# DEVICE-DESKTOP-910Q0FJ.net
KiCad netlist of a schematic drawn in Altium Designer
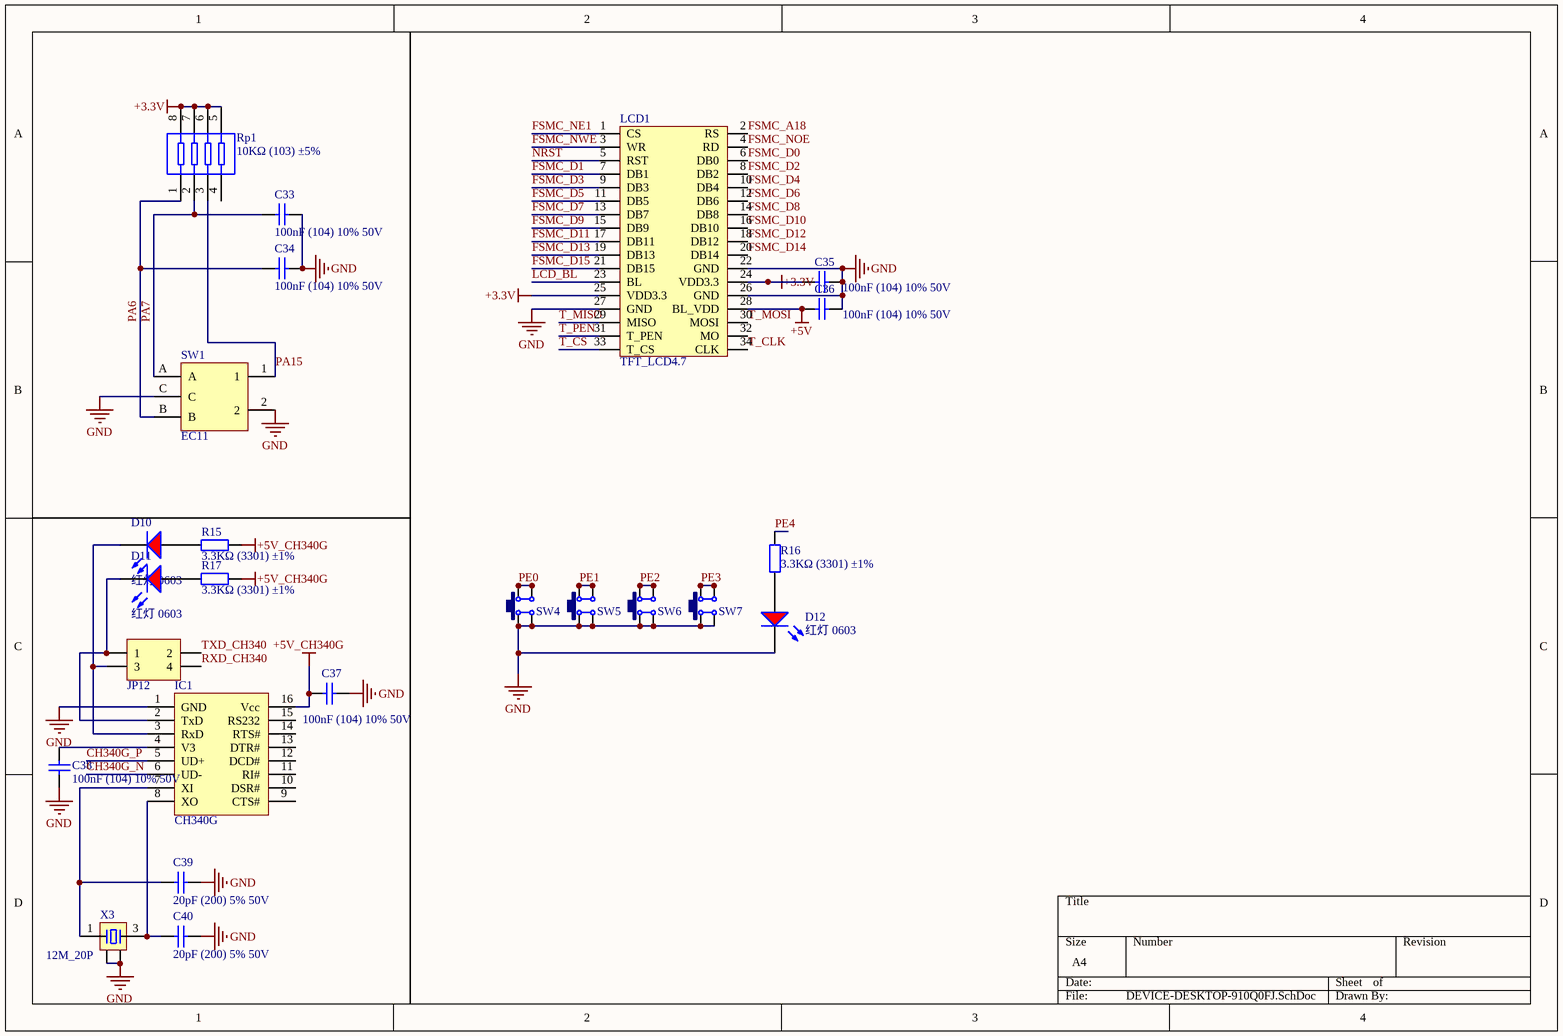
[diagram p0: DEVICE-DESKTOP-910Q0FJ.SchDoc]

(export (version "E")
  (design (tool "Eeschema 10.0.6"))
  (components
    (comp (ref "C33")
      (value "100nF (104) 10% 50V")
      (footprint "0603_C")
      (description "贴片电容")
      (libsource (lib "Cap") (part "0603 100nF (104) 10% 50V"))
    )
    (comp (ref "C34")
      (value "100nF (104) 10% 50V")
      (footprint "0603_C")
      (description "贴片电容")
      (libsource (lib "Cap") (part "0603 100nF (104) 10% 50V"))
    )
    (comp (ref "C35")
      (value "100nF (104) 10% 50V")
      (footprint "0603_C")
      (description "贴片电容")
      (libsource (lib "Cap") (part "0603 100nF (104) 10% 50V"))
    )
    (comp (ref "C36")
      (value "100nF (104) 10% 50V")
      (footprint "0603_C")
      (description "贴片电容")
      (libsource (lib "Cap") (part "0603 100nF (104) 10% 50V"))
    )
    (comp (ref "C37")
      (value "100nF (104) 10% 50V")
      (footprint "0603_C")
      (description "贴片电容")
      (libsource (lib "Cap") (part "0603 100nF (104) 10% 50V"))
    )
    (comp (ref "C38")
      (value "100nF (104) 10% 50V")
      (footprint "0603_C")
      (description "贴片电容")
      (libsource (lib "Cap") (part "0603 100nF (104) 10% 50V"))
    )
    (comp (ref "C39")
      (value "20pF (200) 5% 50V")
      (footprint "0603_C")
      (description "贴片电容")
      (libsource (lib "Cap") (part "0603 20pF (200) 5% 50V"))
    )
    (comp (ref "C40")
      (value "20pF (200) 5% 50V")
      (footprint "0603_C")
      (description "贴片电容")
      (libsource (lib "Cap") (part "0603 20pF (200) 5% 50V"))
    )
    (comp (ref "D10")
      (value "红灯 0603")
      (footprint "0603_LED_S1")
      (description "发光二极管")
      (libsource (lib "LED") (part "0603 红灯"))
    )
    (comp (ref "D11")
      (value "红灯 0603")
      (footprint "0603_LED_S1")
      (description "发光二极管")
      (libsource (lib "LED") (part "0603 红灯"))
    )
    (comp (ref "D12")
      (value "红灯 0603")
      (footprint "0603_LED_S1")
      (description "发光二极管")
      (libsource (lib "LED") (part "0603 红灯"))
    )
    (comp (ref "IC1")
      (value "CH340G")
      (footprint "SOP16_L")
      (description "串口转USB")
      (fields (field (name "版权归属") "源创客"))
      (libsource (lib "1.1   - IC芯片") (part "CH340G"))
    )
    (comp (ref "JP12")
      (value "Header2X2")
      (footprint "HDR2.54-LI-2x2P")
      (description "2*2P接插件")
      (fields (field (name "版权归属") "源创客"))
      (libsource (lib "4.5   - 接插件-脚距2.54") (part "Header 2X2"))
    )
    (comp (ref "LCD1")
      (value "TFT_LCD4.7")
      (footprint "DB2*17-3.5")
      (libsource (lib "STM32F407Z") (part "TFT_LCD4.7"))
    )
    (comp (ref "R15")
      (value "3.3KΩ (3301) ±1%")
      (footprint "0603_R")
      (description "贴片电阻")
      (libsource (lib "RES") (part "0603 3.3KΩ (3301) 1%"))
    )
    (comp (ref "R16")
      (value "3.3KΩ (3301) ±1%")
      (footprint "0603_R")
      (description "贴片电阻")
      (libsource (lib "") (part "0603 3.3KΩ (3301) 1%_1"))
    )
    (comp (ref "R17")
      (value "3.3KΩ (3301) ±1%")
      (footprint "0603_R")
      (description "贴片电阻")
      (libsource (lib "RES") (part "0603 3.3KΩ (3301) 1%"))
    )
    (comp (ref "Rp1")
      (value "10KΩ (103) ±5%")
      (footprint "0603_Rx4")
      (description "贴片排阻")
      (libsource (lib "RES") (part "0603*4  10KΩ (103) 5%"))
    )
    (comp (ref "SW1")
      (value "EC11")
      (footprint "EC11-B")
      (description "数字开关编码器")
      (fields (field (name "版权归属") "源创客"))
      (libsource (lib "5.1   - 按键-开关") (part "EC11"))
    )
    (comp (ref "SW4")
      (value "6x6x5")
      (footprint "TSW DIP-6*6*6")
      (description "直插6x6轻触开关")
      (fields (field (name "版权归属") "源创客"))
      (libsource (lib "5.1   - 按键-开关") (part "TSW DIP-6x6"))
    )
    (comp (ref "SW5")
      (value "6x6x5")
      (footprint "TSW DIP-6*6*6")
      (description "直插6x6轻触开关")
      (fields (field (name "版权归属") "源创客"))
      (libsource (lib "5.1   - 按键-开关") (part "TSW DIP-6x6"))
    )
    (comp (ref "SW6")
      (value "6x6x5")
      (footprint "TSW DIP-6*6*6")
      (description "直插6x6轻触开关")
      (fields (field (name "版权归属") "源创客"))
      (libsource (lib "5.1   - 按键-开关") (part "TSW DIP-6x6"))
    )
    (comp (ref "SW7")
      (value "6x6x5")
      (footprint "TSW DIP-6*6*6")
      (description "直插6x6轻触开关")
      (fields (field (name "版权归属") "源创客"))
      (libsource (lib "5.1   - 按键-开关") (part "TSW DIP-6x6"))
    )
    (comp (ref "X3")
      (value "12M_20P")
      (footprint "OSC 3225-4P")
      (description "4脚无源晶振")
      (fields (field (name "版权归属") "源创客"))
      (libsource (lib "10.1 - 保险丝-晶振") (part "XTAL-4P"))
    )
  )
  (nets
    (net (code "1") (name "+3.3V") (class "Default")
      (node (ref "C35") (pin "1") (pinfunction "1_1") (pintype "passive"))
      (node (ref "LCD1") (pin "24") (pinfunction "VDD3.3_24") (pintype "passive"))
      (node (ref "LCD1") (pin "25") (pinfunction "VDD3.3_25") (pintype "passive"))
      (node (ref "Rp1") (pin "5") (pinfunction "5_5") (pintype "passive"))
      (node (ref "Rp1") (pin "6") (pinfunction "6_6") (pintype "passive"))
      (node (ref "Rp1") (pin "7") (pinfunction "7_7") (pintype "passive"))
      (node (ref "Rp1") (pin "8") (pinfunction "8_8") (pintype "passive"))
    )
    (net (code "2") (name "+5V") (class "Default")
      (node (ref "C36") (pin "2") (pinfunction "2_2") (pintype "passive"))
      (node (ref "LCD1") (pin "28") (pinfunction "BL_VDD_28") (pintype "passive"))
    )
    (net (code "3") (name "+5V_CH340G") (class "Default")
      (node (ref "C37") (pin "1") (pinfunction "1_1") (pintype "passive"))
      (node (ref "IC1") (pin "16") (pinfunction "Vcc_16") (pintype "passive"))
      (node (ref "R15") (pin "2") (pinfunction "2_2") (pintype "passive"))
      (node (ref "R17") (pin "2") (pinfunction "2_2") (pintype "passive"))
    )
    (net (code "4") (name "/CH340G_N") (class "Default")
      (node (ref "IC1") (pin "6") (pinfunction "UD-_6") (pintype "passive"))
    )
    (net (code "5") (name "/CH340G_P") (class "Default")
      (node (ref "IC1") (pin "5") (pinfunction "UD+_5") (pintype "passive"))
    )
    (net (code "6") (name "/FSMC_A18") (class "Default")
      (node (ref "LCD1") (pin "2") (pinfunction "RS_2") (pintype "passive"))
    )
    (net (code "7") (name "/FSMC_D0") (class "Default")
      (node (ref "LCD1") (pin "6") (pinfunction "DB0_6") (pintype "passive"))
    )
    (net (code "8") (name "/FSMC_D1") (class "Default")
      (node (ref "LCD1") (pin "7") (pinfunction "DB1_7") (pintype "passive"))
    )
    (net (code "9") (name "/FSMC_D2") (class "Default")
      (node (ref "LCD1") (pin "8") (pinfunction "DB2_8") (pintype "passive"))
    )
    (net (code "10") (name "/FSMC_D3") (class "Default")
      (node (ref "LCD1") (pin "9") (pinfunction "DB3_9") (pintype "passive"))
    )
    (net (code "11") (name "/FSMC_D4") (class "Default")
      (node (ref "LCD1") (pin "10") (pinfunction "DB4_10") (pintype "passive"))
    )
    (net (code "12") (name "/FSMC_D5") (class "Default")
      (node (ref "LCD1") (pin "11") (pinfunction "DB5_11") (pintype "passive"))
    )
    (net (code "13") (name "/FSMC_D6") (class "Default")
      (node (ref "LCD1") (pin "12") (pinfunction "DB6_12") (pintype "passive"))
    )
    (net (code "14") (name "/FSMC_D7") (class "Default")
      (node (ref "LCD1") (pin "13") (pinfunction "DB7_13") (pintype "passive"))
    )
    (net (code "15") (name "/FSMC_D8") (class "Default")
      (node (ref "LCD1") (pin "14") (pinfunction "DB8_14") (pintype "passive"))
    )
    (net (code "16") (name "/FSMC_D9") (class "Default")
      (node (ref "LCD1") (pin "15") (pinfunction "DB9_15") (pintype "passive"))
    )
    (net (code "17") (name "/FSMC_D10") (class "Default")
      (node (ref "LCD1") (pin "16") (pinfunction "DB10_16") (pintype "passive"))
    )
    (net (code "18") (name "/FSMC_D11") (class "Default")
      (node (ref "LCD1") (pin "17") (pinfunction "DB11_17") (pintype "passive"))
    )
    (net (code "19") (name "/FSMC_D12") (class "Default")
      (node (ref "LCD1") (pin "18") (pinfunction "DB12_18") (pintype "passive"))
    )
    (net (code "20") (name "/FSMC_D13") (class "Default")
      (node (ref "LCD1") (pin "19") (pinfunction "DB13_19") (pintype "passive"))
    )
    (net (code "21") (name "/FSMC_D14") (class "Default")
      (node (ref "LCD1") (pin "20") (pinfunction "DB14_20") (pintype "passive"))
    )
    (net (code "22") (name "/FSMC_D15") (class "Default")
      (node (ref "LCD1") (pin "21") (pinfunction "DB15_21") (pintype "passive"))
    )
    (net (code "23") (name "/FSMC_NE1") (class "Default")
      (node (ref "LCD1") (pin "1") (pinfunction "CS_1") (pintype "passive"))
    )
    (net (code "24") (name "/FSMC_NOE") (class "Default")
      (node (ref "LCD1") (pin "4") (pinfunction "RD_4") (pintype "passive"))
    )
    (net (code "25") (name "/FSMC_NWE") (class "Default")
      (node (ref "LCD1") (pin "3") (pinfunction "WR_3") (pintype "passive"))
    )
    (net (code "26") (name "/LCD_BL") (class "Default")
      (node (ref "LCD1") (pin "23") (pinfunction "BL_23") (pintype "passive"))
    )
    (net (code "27") (name "/NRST") (class "Default")
      (node (ref "LCD1") (pin "5") (pinfunction "RST_5") (pintype "passive"))
    )
    (net (code "28") (name "/PA6") (class "Default")
      (node (ref "C34") (pin "2") (pinfunction "2_2") (pintype "passive"))
      (node (ref "Rp1") (pin "1") (pinfunction "1_1") (pintype "passive"))
      (node (ref "SW1") (pin "B") (pinfunction "B_B") (pintype "passive"))
    )
    (net (code "29") (name "/PA7") (class "Default")
      (node (ref "C33") (pin "2") (pinfunction "2_2") (pintype "passive"))
      (node (ref "Rp1") (pin "2") (pinfunction "2_2") (pintype "passive"))
      (node (ref "SW1") (pin "A") (pinfunction "A_A") (pintype "passive"))
    )
    (net (code "30") (name "/PA15") (class "Default")
      (node (ref "Rp1") (pin "3") (pinfunction "3_3") (pintype "passive"))
      (node (ref "SW1") (pin "1") (pinfunction "1_1") (pintype "passive"))
    )
    (net (code "31") (name "/PE0") (class "Default")
      (node (ref "SW4") (pin "2") (pinfunction "2_2") (pintype "passive"))
      (node (ref "SW4") (pin "3") (pinfunction "3_3") (pintype "passive"))
    )
    (net (code "32") (name "/PE1") (class "Default")
      (node (ref "SW5") (pin "2") (pinfunction "2_2") (pintype "passive"))
      (node (ref "SW5") (pin "3") (pinfunction "3_3") (pintype "passive"))
    )
    (net (code "33") (name "/PE2") (class "Default")
      (node (ref "SW6") (pin "2") (pinfunction "2_2") (pintype "passive"))
      (node (ref "SW6") (pin "3") (pinfunction "3_3") (pintype "passive"))
    )
    (net (code "34") (name "/PE3") (class "Default")
      (node (ref "SW7") (pin "2") (pinfunction "2_2") (pintype "passive"))
      (node (ref "SW7") (pin "3") (pinfunction "3_3") (pintype "passive"))
    )
    (net (code "35") (name "/PE4") (class "Default")
      (node (ref "R16") (pin "2") (pinfunction "2_2") (pintype "passive"))
    )
    (net (code "36") (name "/RXD_CH340") (class "Default")
      (node (ref "JP12") (pin "4") (pinfunction "4_4") (pintype "passive"))
    )
    (net (code "37") (name "/TXD_CH340") (class "Default")
      (node (ref "JP12") (pin "2") (pinfunction "2_2") (pintype "passive"))
    )
    (net (code "38") (name "/T_CLK") (class "Default")
      (node (ref "LCD1") (pin "34") (pinfunction "CLK_34") (pintype "passive"))
    )
    (net (code "39") (name "/T_CS") (class "Default")
      (node (ref "LCD1") (pin "33") (pinfunction "T_CS_33") (pintype "passive"))
    )
    (net (code "40") (name "/T_MISO") (class "Default")
      (node (ref "LCD1") (pin "29") (pinfunction "MISO_29") (pintype "passive"))
    )
    (net (code "41") (name "/T_MOSI") (class "Default")
      (node (ref "LCD1") (pin "30") (pinfunction "MOSI_30") (pintype "passive"))
    )
    (net (code "42") (name "/T_PEN") (class "Default")
      (node (ref "LCD1") (pin "31") (pinfunction "T_PEN_31") (pintype "passive"))
    )
    (net (code "43") (name "GND") (class "Default")
      (node (ref "C33") (pin "1") (pinfunction "1_1") (pintype "passive"))
      (node (ref "C34") (pin "1") (pinfunction "1_1") (pintype "passive"))
      (node (ref "C35") (pin "2") (pinfunction "2_2") (pintype "passive"))
      (node (ref "C36") (pin "1") (pinfunction "1_1") (pintype "passive"))
      (node (ref "C37") (pin "2") (pinfunction "2_2") (pintype "passive"))
      (node (ref "C38") (pin "2") (pinfunction "2_2") (pintype "passive"))
      (node (ref "C39") (pin "1") (pinfunction "1_1") (pintype "passive"))
      (node (ref "C40") (pin "1") (pinfunction "1_1") (pintype "passive"))
      (node (ref "D12") (pin "K") (pinfunction "K_K") (pintype "passive"))
      (node (ref "IC1") (pin "1") (pinfunction "GND_1") (pintype "passive"))
      (node (ref "LCD1") (pin "22") (pinfunction "GND_22") (pintype "passive"))
      (node (ref "LCD1") (pin "26") (pinfunction "GND_26") (pintype "passive"))
      (node (ref "LCD1") (pin "27") (pinfunction "GND_27") (pintype "passive"))
      (node (ref "SW1") (pin "2") (pinfunction "2_2") (pintype "passive"))
      (node (ref "SW1") (pin "C") (pinfunction "C_C") (pintype "passive"))
      (node (ref "SW4") (pin "1") (pinfunction "1_1") (pintype "passive"))
      (node (ref "SW4") (pin "4") (pinfunction "4_4") (pintype "passive"))
      (node (ref "SW5") (pin "1") (pinfunction "1_1") (pintype "passive"))
      (node (ref "SW5") (pin "4") (pinfunction "4_4") (pintype "passive"))
      (node (ref "SW6") (pin "1") (pinfunction "1_1") (pintype "passive"))
      (node (ref "SW6") (pin "4") (pinfunction "4_4") (pintype "passive"))
      (node (ref "SW7") (pin "1") (pinfunction "1_1") (pintype "passive"))
      (node (ref "SW7") (pin "4") (pinfunction "4_4") (pintype "passive"))
      (node (ref "X3") (pin "2") (pinfunction "2_2") (pintype "passive"))
      (node (ref "X3") (pin "4") (pinfunction "4_4") (pintype "passive"))
    )
    (net (code "44") (name "Net-(D10-PadA)") (class "Default")
      (node (ref "D10") (pin "A") (pinfunction "A_A") (pintype "passive"))
      (node (ref "R15") (pin "1") (pinfunction "1_1") (pintype "passive"))
    )
    (net (code "45") (name "Net-(D11-PadA)") (class "Default")
      (node (ref "D11") (pin "A") (pinfunction "A_A") (pintype "passive"))
      (node (ref "R17") (pin "1") (pinfunction "1_1") (pintype "passive"))
    )
    (net (code "46") (name "Net-(D12-PadA)") (class "Default")
      (node (ref "D12") (pin "A") (pinfunction "A_A") (pintype "passive"))
      (node (ref "R16") (pin "1") (pinfunction "1_1") (pintype "passive"))
    )
    (net (code "47") (name "Net-(IC1-RxD)") (class "Default")
      (node (ref "D10") (pin "K") (pinfunction "K_K") (pintype "passive"))
      (node (ref "IC1") (pin "3") (pinfunction "RxD_3") (pintype "passive"))
      (node (ref "JP12") (pin "3") (pinfunction "3_3") (pintype "passive"))
    )
    (net (code "48") (name "Net-(IC1-TxD)") (class "Default")
      (node (ref "D11") (pin "K") (pinfunction "K_K") (pintype "passive"))
      (node (ref "IC1") (pin "2") (pinfunction "TxD_2") (pintype "passive"))
      (node (ref "JP12") (pin "1") (pinfunction "1_1") (pintype "passive"))
    )
    (net (code "49") (name "Net-(IC1-V3)") (class "Default")
      (node (ref "C38") (pin "1") (pinfunction "1_1") (pintype "passive"))
      (node (ref "IC1") (pin "4") (pinfunction "V3_4") (pintype "passive"))
    )
    (net (code "50") (name "Net-(IC1-XI)") (class "Default")
      (node (ref "C39") (pin "2") (pinfunction "2_2") (pintype "passive"))
      (node (ref "IC1") (pin "7") (pinfunction "XI_7") (pintype "passive"))
      (node (ref "X3") (pin "1") (pinfunction "1_1") (pintype "passive"))
    )
    (net (code "51") (name "Net-(IC1-XO)") (class "Default")
      (node (ref "C40") (pin "2") (pinfunction "2_2") (pintype "passive"))
      (node (ref "IC1") (pin "8") (pinfunction "XO_8") (pintype "passive"))
      (node (ref "X3") (pin "3") (pinfunction "3_3") (pintype "passive"))
    )
    (net (code "52") (name "unconnected-(IC1-CTS#-Pad9)") (class "Default")
      (node (ref "IC1") (pin "9") (pinfunction "CTS#_9") (pintype "passive"))
    )
    (net (code "53") (name "unconnected-(IC1-DCD#-Pad12)") (class "Default")
      (node (ref "IC1") (pin "12") (pinfunction "DCD#_12") (pintype "passive"))
    )
    (net (code "54") (name "unconnected-(IC1-DSR#-Pad10)") (class "Default")
      (node (ref "IC1") (pin "10") (pinfunction "DSR#_10") (pintype "passive"))
    )
    (net (code "55") (name "unconnected-(IC1-DTR#-Pad13)") (class "Default")
      (node (ref "IC1") (pin "13") (pinfunction "DTR#_13") (pintype "passive"))
    )
    (net (code "56") (name "unconnected-(IC1-RI#-Pad11)") (class "Default")
      (node (ref "IC1") (pin "11") (pinfunction "RI#_11") (pintype "passive"))
    )
    (net (code "57") (name "unconnected-(IC1-RS232-Pad15)") (class "Default")
      (node (ref "IC1") (pin "15") (pinfunction "RS232_15") (pintype "passive"))
    )
    (net (code "58") (name "unconnected-(IC1-RTS#-Pad14)") (class "Default")
      (node (ref "IC1") (pin "14") (pinfunction "RTS#_14") (pintype "passive"))
    )
    (net (code "59") (name "unconnected-(LCD1-MO-Pad32)") (class "Default")
      (node (ref "LCD1") (pin "32") (pinfunction "MO_32") (pintype "passive"))
    )
    (net (code "60") (name "unconnected-(Rp1-Pad4)") (class "Default")
      (node (ref "Rp1") (pin "4") (pinfunction "4_4") (pintype "passive"))
    )
  )
)
